# Power_Outputs.net
KiCad netlist of a schematic drawn in Altium Designer
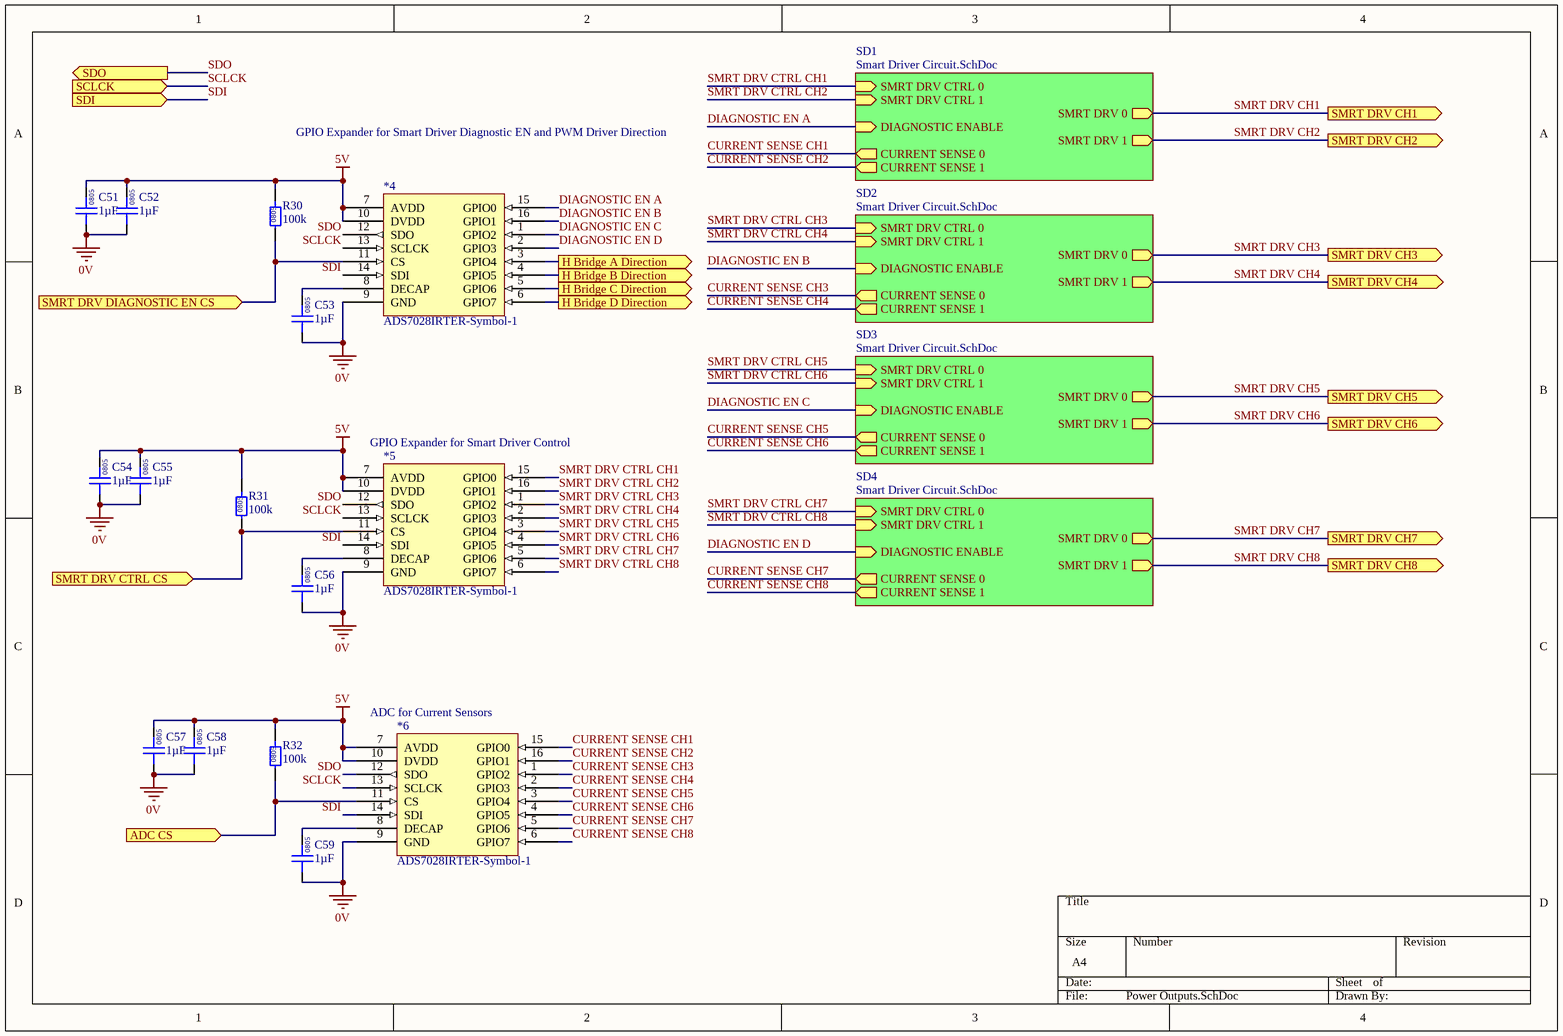
[diagram p0: Power Outputs.SchDoc]

(export (version "E")
  (design (tool "Eeschema 10.0.6"))
  (components
    (comp (ref "*4")
      (value "ADS7028IRTER-Symbol-1")
      (footprint "QFN50P300X300X80_HS-17N")
      (description "IC ADC 12BIT SAR 16WQFN")
      (fields (field (name "PART NUMBER") "ADS7028IRTER") (field (name "MANUFACTURER") "Texas Instruments"))
      (libsource (lib "ts_standard_library") (part "ADS7028IRTER"))
    )
    (comp (ref "*5")
      (value "ADS7028IRTER-Symbol-1")
      (footprint "QFN50P300X300X80_HS-17N")
      (description "IC ADC 12BIT SAR 16WQFN")
      (fields (field (name "PART NUMBER") "ADS7028IRTER") (field (name "MANUFACTURER") "Texas Instruments"))
      (libsource (lib "ts_standard_library") (part "ADS7028IRTER"))
    )
    (comp (ref "*6")
      (value "ADS7028IRTER-Symbol-1")
      (footprint "QFN50P300X300X80_HS-17N")
      (description "IC ADC 12BIT SAR 16WQFN")
      (fields (field (name "PART NUMBER") "ADS7028IRTER") (field (name "MANUFACTURER") "Texas Instruments"))
      (libsource (lib "ts_standard_library") (part "ADS7028IRTER"))
    )
    (comp (ref "C51")
      (value "1µF")
      (footprint "0805")
      (fields
        (field (name "PART NUMBER") "GCM21BR71H105KA03L")
        (field (name "MANUFACTURER") "muRata")
        (field (name "TOLERANCE") "±10%")
      )
      (libsource (lib "ts_standard_library") (part "Capacitor 0805"))
    )
    (comp (ref "C52")
      (value "1µF")
      (footprint "0805")
      (fields
        (field (name "PART NUMBER") "GCM21BR71H105KA03L")
        (field (name "MANUFACTURER") "muRata")
        (field (name "TOLERANCE") "±10%")
      )
      (libsource (lib "ts_standard_library") (part "Capacitor 0805"))
    )
    (comp (ref "C53")
      (value "1µF")
      (footprint "0805")
      (fields
        (field (name "PART NUMBER") "GCM21BR71H105KA03L")
        (field (name "MANUFACTURER") "muRata")
        (field (name "TOLERANCE") "±10%")
      )
      (libsource (lib "ts_standard_library") (part "Capacitor 0805"))
    )
    (comp (ref "C54")
      (value "1µF")
      (footprint "0805")
      (fields
        (field (name "PART NUMBER") "GCM21BR71H105KA03L")
        (field (name "MANUFACTURER") "muRata")
        (field (name "TOLERANCE") "±10%")
      )
      (libsource (lib "ts_standard_library") (part "Capacitor 0805"))
    )
    (comp (ref "C55")
      (value "1µF")
      (footprint "0805")
      (fields
        (field (name "PART NUMBER") "GCM21BR71H105KA03L")
        (field (name "MANUFACTURER") "muRata")
        (field (name "TOLERANCE") "±10%")
      )
      (libsource (lib "ts_standard_library") (part "Capacitor 0805"))
    )
    (comp (ref "C56")
      (value "1µF")
      (footprint "0805")
      (fields
        (field (name "PART NUMBER") "GCM21BR71H105KA03L")
        (field (name "MANUFACTURER") "muRata")
        (field (name "TOLERANCE") "±10%")
      )
      (libsource (lib "ts_standard_library") (part "Capacitor 0805"))
    )
    (comp (ref "C57")
      (value "1µF")
      (footprint "0805")
      (fields
        (field (name "PART NUMBER") "GCM21BR71H105KA03L")
        (field (name "MANUFACTURER") "muRata")
        (field (name "TOLERANCE") "±10%")
      )
      (libsource (lib "ts_standard_library") (part "Capacitor 0805"))
    )
    (comp (ref "C58")
      (value "1µF")
      (footprint "0805")
      (fields
        (field (name "PART NUMBER") "GCM21BR71H105KA03L")
        (field (name "MANUFACTURER") "muRata")
        (field (name "TOLERANCE") "±10%")
      )
      (libsource (lib "ts_standard_library") (part "Capacitor 0805"))
    )
    (comp (ref "C59")
      (value "1µF")
      (footprint "0805")
      (fields
        (field (name "PART NUMBER") "GCM21BR71H105KA03L")
        (field (name "MANUFACTURER") "muRata")
        (field (name "TOLERANCE") "±10%")
      )
      (libsource (lib "ts_standard_library") (part "Capacitor 0805"))
    )
    (comp (ref "R30")
      (value "100k")
      (footprint "0805")
      (fields
        (field (name "PART NUMBER") "RC0805FR07100KL")
        (field (name "MANUFACTURER") "YAGEO")
        (field (name "TOLERANCE") "0.01")
      )
      (libsource (lib "ts_standard_library") (part "Resistor 0805"))
    )
    (comp (ref "R31")
      (value "100k")
      (footprint "0805")
      (fields
        (field (name "PART NUMBER") "RC0805FR07100KL")
        (field (name "MANUFACTURER") "YAGEO")
        (field (name "TOLERANCE") "0.01")
      )
      (libsource (lib "ts_standard_library") (part "Resistor 0805"))
    )
    (comp (ref "R32")
      (value "100k")
      (footprint "0805")
      (fields
        (field (name "PART NUMBER") "RC0805FR07100KL")
        (field (name "MANUFACTURER") "YAGEO")
        (field (name "TOLERANCE") "0.01")
      )
      (libsource (lib "ts_standard_library") (part "Resistor 0805"))
    )
  )
  (nets
    (net (code "1") (name "/ADC CS") (class "Default")
      (node (ref "*6") (pin "11") (pinfunction "CS_11") (pintype "input"))
      (node (ref "R32") (pin "1") (pinfunction "1_1") (pintype "passive"))
    )
    (net (code "2") (name "/CURRENT SENSE CH1") (class "Default")
      (node (ref "*6") (pin "15") (pinfunction "GPIO0_15") (pintype "input"))
    )
    (net (code "3") (name "/CURRENT SENSE CH2") (class "Default")
      (node (ref "*6") (pin "16") (pinfunction "GPIO1_16") (pintype "input"))
    )
    (net (code "4") (name "/CURRENT SENSE CH3") (class "Default")
      (node (ref "*6") (pin "1") (pinfunction "GPIO2_1") (pintype "input"))
    )
    (net (code "5") (name "/CURRENT SENSE CH4") (class "Default")
      (node (ref "*6") (pin "2") (pinfunction "GPIO3_2") (pintype "input"))
    )
    (net (code "6") (name "/CURRENT SENSE CH5") (class "Default")
      (node (ref "*6") (pin "3") (pinfunction "GPIO4_3") (pintype "input"))
    )
    (net (code "7") (name "/CURRENT SENSE CH6") (class "Default")
      (node (ref "*6") (pin "4") (pinfunction "GPIO5_4") (pintype "input"))
    )
    (net (code "8") (name "/CURRENT SENSE CH7") (class "Default")
      (node (ref "*6") (pin "5") (pinfunction "GPIO6_5") (pintype "input"))
    )
    (net (code "9") (name "/CURRENT SENSE CH8") (class "Default")
      (node (ref "*6") (pin "6") (pinfunction "GPIO7_6") (pintype "input"))
    )
    (net (code "10") (name "/DIAGNOSTIC EN A") (class "Default")
      (node (ref "*4") (pin "15") (pinfunction "GPIO0_15") (pintype "input"))
    )
    (net (code "11") (name "/DIAGNOSTIC EN B") (class "Default")
      (node (ref "*4") (pin "16") (pinfunction "GPIO1_16") (pintype "input"))
    )
    (net (code "12") (name "/DIAGNOSTIC EN C") (class "Default")
      (node (ref "*4") (pin "1") (pinfunction "GPIO2_1") (pintype "input"))
    )
    (net (code "13") (name "/DIAGNOSTIC EN D") (class "Default")
      (node (ref "*4") (pin "2") (pinfunction "GPIO3_2") (pintype "input"))
    )
    (net (code "14") (name "/H Bridge A Direction") (class "Default")
      (node (ref "*4") (pin "3") (pinfunction "GPIO4_3") (pintype "input"))
    )
    (net (code "15") (name "/H Bridge B Direction") (class "Default")
      (node (ref "*4") (pin "4") (pinfunction "GPIO5_4") (pintype "input"))
    )
    (net (code "16") (name "/H Bridge C Direction") (class "Default")
      (node (ref "*4") (pin "5") (pinfunction "GPIO6_5") (pintype "input"))
    )
    (net (code "17") (name "/H Bridge D Direction") (class "Default")
      (node (ref "*4") (pin "6") (pinfunction "GPIO7_6") (pintype "input"))
    )
    (net (code "18") (name "/SCLCK") (class "Default")
      (node (ref "*4") (pin "13") (pinfunction "SCLCK_13") (pintype "input"))
      (node (ref "*5") (pin "13") (pinfunction "SCLCK_13") (pintype "input"))
      (node (ref "*6") (pin "13") (pinfunction "SCLCK_13") (pintype "input"))
    )
    (net (code "19") (name "/SDI") (class "Default")
      (node (ref "*4") (pin "14") (pinfunction "SDI_14") (pintype "input"))
      (node (ref "*5") (pin "14") (pinfunction "SDI_14") (pintype "input"))
      (node (ref "*6") (pin "14") (pinfunction "SDI_14") (pintype "input"))
    )
    (net (code "20") (name "/SDO") (class "Default")
      (node (ref "*4") (pin "12") (pinfunction "SDO_12") (pintype "output"))
      (node (ref "*5") (pin "12") (pinfunction "SDO_12") (pintype "output"))
      (node (ref "*6") (pin "12") (pinfunction "SDO_12") (pintype "output"))
    )
    (net (code "29") (name "/SMRT DRV CTRL CH1") (class "Default")
      (node (ref "*5") (pin "15") (pinfunction "GPIO0_15") (pintype "input"))
    )
    (net (code "30") (name "/SMRT DRV CTRL CH2") (class "Default")
      (node (ref "*5") (pin "16") (pinfunction "GPIO1_16") (pintype "input"))
    )
    (net (code "31") (name "/SMRT DRV CTRL CH3") (class "Default")
      (node (ref "*5") (pin "1") (pinfunction "GPIO2_1") (pintype "input"))
    )
    (net (code "32") (name "/SMRT DRV CTRL CH4") (class "Default")
      (node (ref "*5") (pin "2") (pinfunction "GPIO3_2") (pintype "input"))
    )
    (net (code "33") (name "/SMRT DRV CTRL CH5") (class "Default")
      (node (ref "*5") (pin "3") (pinfunction "GPIO4_3") (pintype "input"))
    )
    (net (code "34") (name "/SMRT DRV CTRL CH6") (class "Default")
      (node (ref "*5") (pin "4") (pinfunction "GPIO5_4") (pintype "input"))
    )
    (net (code "35") (name "/SMRT DRV CTRL CH7") (class "Default")
      (node (ref "*5") (pin "5") (pinfunction "GPIO6_5") (pintype "input"))
    )
    (net (code "36") (name "/SMRT DRV CTRL CH8") (class "Default")
      (node (ref "*5") (pin "6") (pinfunction "GPIO7_6") (pintype "input"))
    )
    (net (code "37") (name "/SMRT DRV CTRL CS") (class "Default")
      (node (ref "*5") (pin "11") (pinfunction "CS_11") (pintype "input"))
      (node (ref "R31") (pin "1") (pinfunction "1_1") (pintype "passive"))
    )
    (net (code "38") (name "/SMRT DRV DIAGNOSTIC EN CS") (class "Default")
      (node (ref "*4") (pin "11") (pinfunction "CS_11") (pintype "input"))
      (node (ref "R30") (pin "1") (pinfunction "1_1") (pintype "passive"))
    )
    (net (code "39") (name "0V") (class "Default")
      (node (ref "*4") (pin "9") (pinfunction "GND_9") (pintype "power_in"))
      (node (ref "*5") (pin "9") (pinfunction "GND_9") (pintype "power_in"))
      (node (ref "*6") (pin "9") (pinfunction "GND_9") (pintype "power_in"))
      (node (ref "C51") (pin "1") (pinfunction "1_1") (pintype "passive"))
      (node (ref "C52") (pin "1") (pinfunction "1_1") (pintype "passive"))
      (node (ref "C53") (pin "1") (pinfunction "1_1") (pintype "passive"))
      (node (ref "C54") (pin "1") (pinfunction "1_1") (pintype "passive"))
      (node (ref "C55") (pin "1") (pinfunction "1_1") (pintype "passive"))
      (node (ref "C56") (pin "1") (pinfunction "1_1") (pintype "passive"))
      (node (ref "C57") (pin "1") (pinfunction "1_1") (pintype "passive"))
      (node (ref "C58") (pin "1") (pinfunction "1_1") (pintype "passive"))
      (node (ref "C59") (pin "1") (pinfunction "1_1") (pintype "passive"))
    )
    (net (code "40") (name "5V") (class "Default")
      (node (ref "*4") (pin "10") (pinfunction "DVDD_10") (pintype "power_in"))
      (node (ref "*4") (pin "7") (pinfunction "AVDD_7") (pintype "power_in"))
      (node (ref "*5") (pin "10") (pinfunction "DVDD_10") (pintype "power_in"))
      (node (ref "*5") (pin "7") (pinfunction "AVDD_7") (pintype "power_in"))
      (node (ref "*6") (pin "10") (pinfunction "DVDD_10") (pintype "power_in"))
      (node (ref "*6") (pin "7") (pinfunction "AVDD_7") (pintype "power_in"))
      (node (ref "C51") (pin "2") (pinfunction "2_2") (pintype "passive"))
      (node (ref "C52") (pin "2") (pinfunction "2_2") (pintype "passive"))
      (node (ref "C54") (pin "2") (pinfunction "2_2") (pintype "passive"))
      (node (ref "C55") (pin "2") (pinfunction "2_2") (pintype "passive"))
      (node (ref "C57") (pin "2") (pinfunction "2_2") (pintype "passive"))
      (node (ref "C58") (pin "2") (pinfunction "2_2") (pintype "passive"))
      (node (ref "R30") (pin "2") (pinfunction "2_2") (pintype "passive"))
      (node (ref "R31") (pin "2") (pinfunction "2_2") (pintype "passive"))
      (node (ref "R32") (pin "2") (pinfunction "2_2") (pintype "passive"))
    )
    (net (code "41") (name "Net-(*4-DECAP)") (class "Default")
      (node (ref "*4") (pin "8") (pinfunction "DECAP_8") (pintype "power_in"))
      (node (ref "C53") (pin "2") (pinfunction "2_2") (pintype "passive"))
    )
    (net (code "42") (name "Net-(*5-DECAP)") (class "Default")
      (node (ref "*5") (pin "8") (pinfunction "DECAP_8") (pintype "power_in"))
      (node (ref "C56") (pin "2") (pinfunction "2_2") (pintype "passive"))
    )
    (net (code "43") (name "Net-(*6-DECAP)") (class "Default")
      (node (ref "*6") (pin "8") (pinfunction "DECAP_8") (pintype "power_in"))
      (node (ref "C59") (pin "2") (pinfunction "2_2") (pintype "passive"))
    )
  )
)
